# sbc.net
KiCad netlist of a schematic drawn in EAGLE
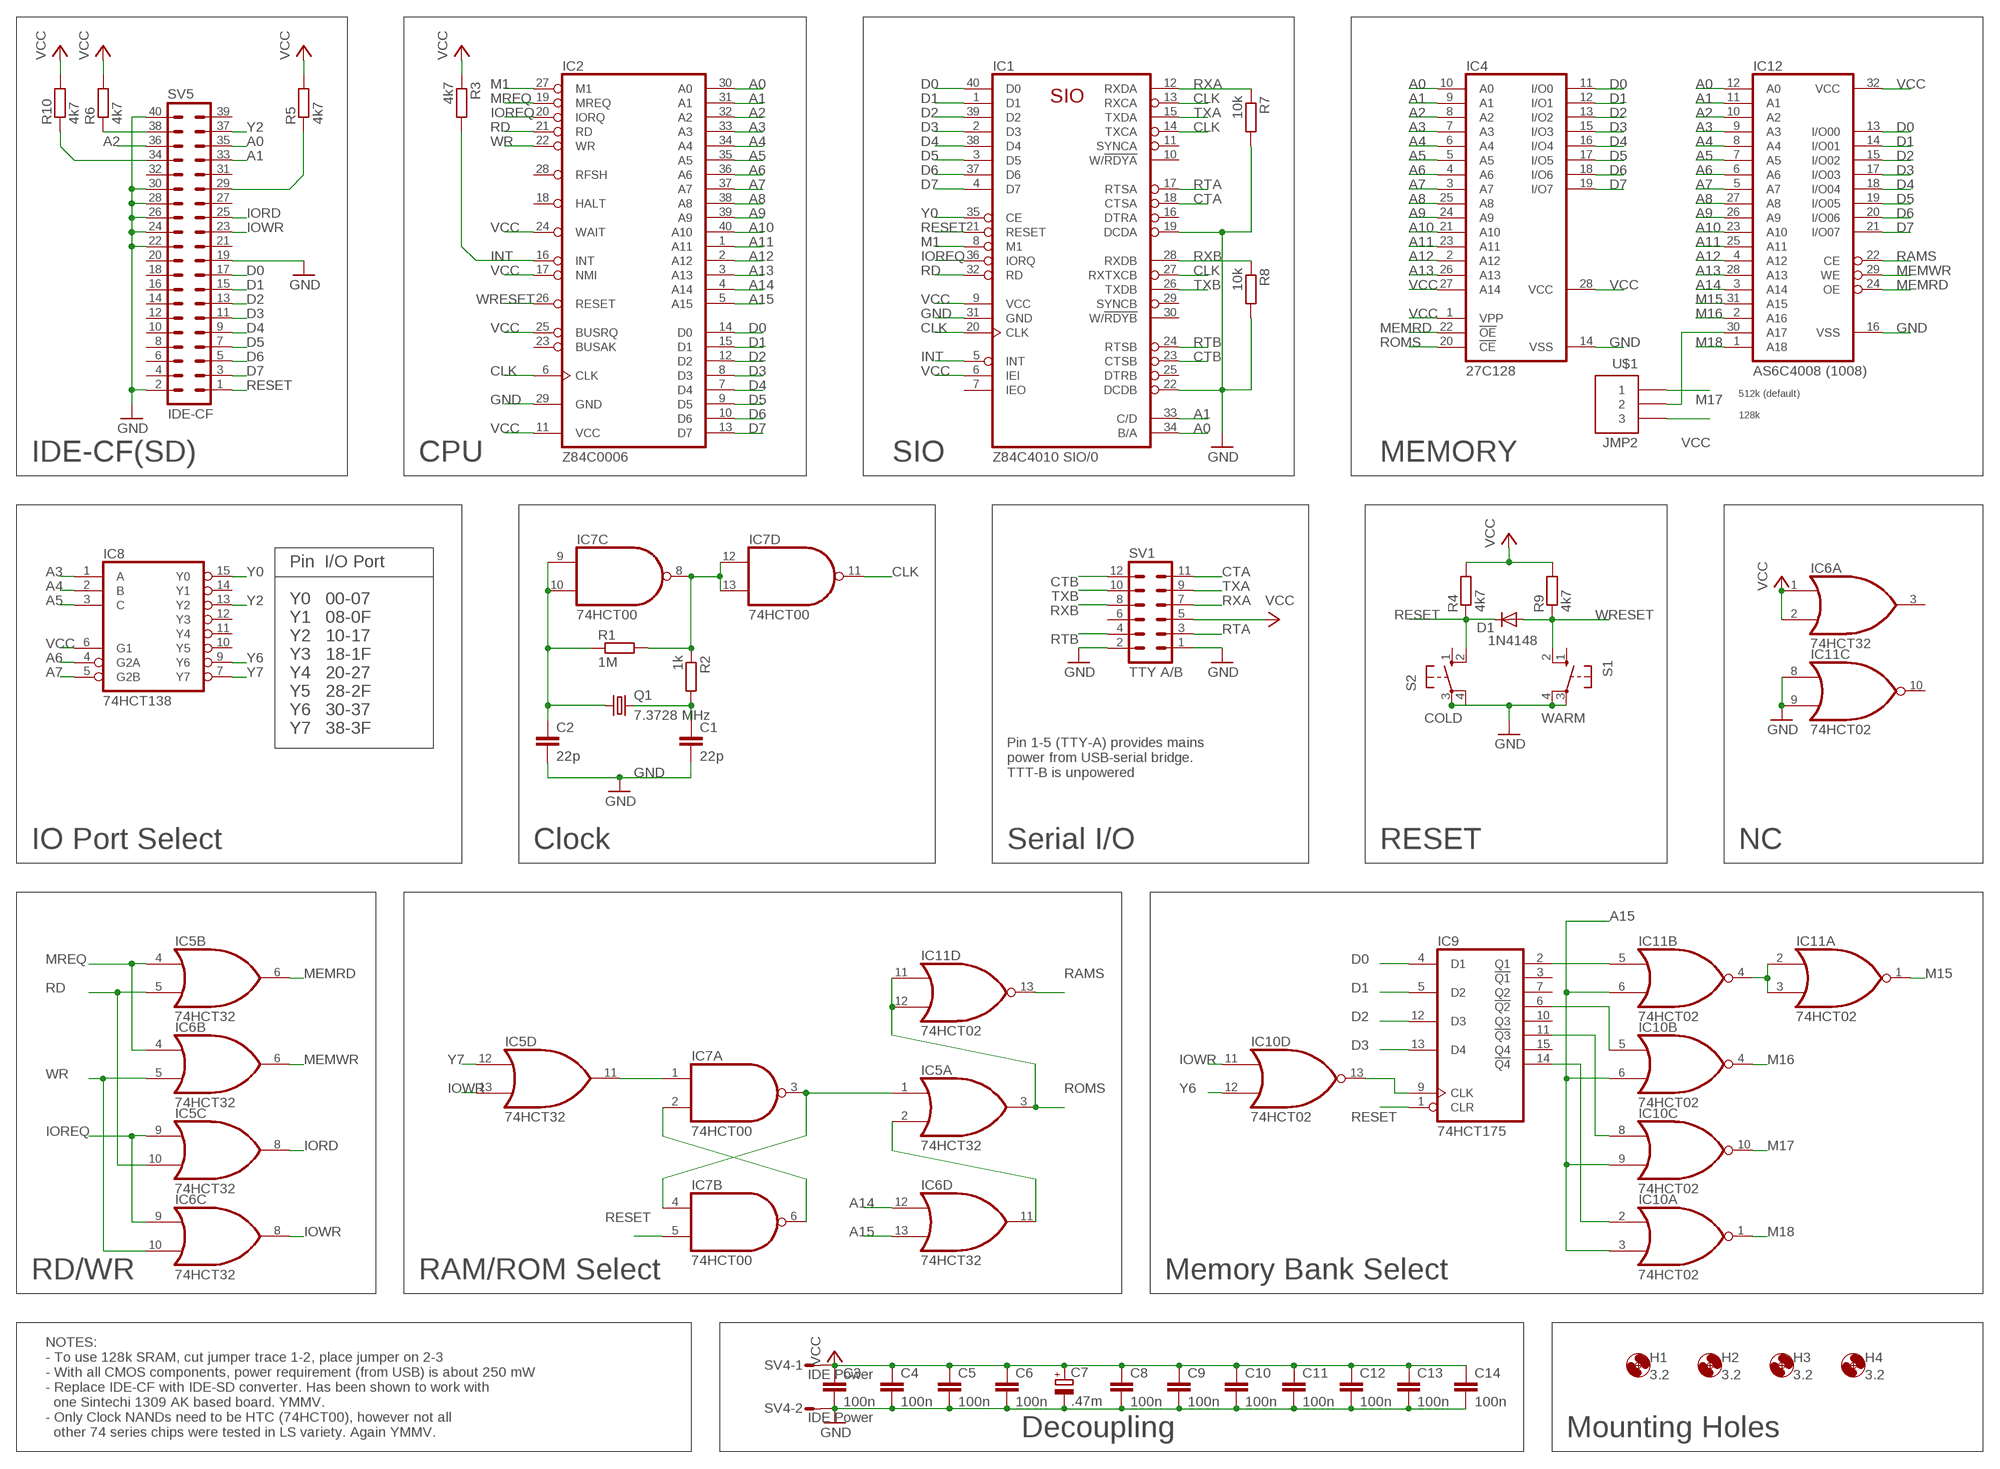
[diagram p0: schematic, sheet 1]

(export (version "E")
  (design (tool "Eeschema 10.0.6"))
  (components
    (comp (ref "C1")
      (value "22p")
      (footprint "eagle-import:C025-024X044")
      (libsource (lib "eagle-import") (part "C-EU025-024X044"))
    )
    (comp (ref "C2")
      (value "22p")
      (footprint "eagle-import:C025-024X044")
      (libsource (lib "eagle-import") (part "C-EU025-024X044"))
    )
    (comp (ref "C3")
      (value "100n")
      (footprint "eagle-import:C050-025X075")
      (libsource (lib "eagle-import") (part "C-EU050-025X075"))
    )
    (comp (ref "C4")
      (value "100n")
      (footprint "eagle-import:C050-025X075")
      (libsource (lib "eagle-import") (part "C-EU050-025X075"))
    )
    (comp (ref "C5")
      (value "100n")
      (footprint "eagle-import:C050-025X075")
      (libsource (lib "eagle-import") (part "C-EU050-025X075"))
    )
    (comp (ref "C6")
      (value "100n")
      (footprint "eagle-import:C050-025X075")
      (libsource (lib "eagle-import") (part "C-EU050-025X075"))
    )
    (comp (ref "C7")
      (value ".47m")
      (footprint "eagle-import:E2,5-6E")
      (libsource (lib "eagle-import") (part "CPOL-EUE2,5-6E"))
    )
    (comp (ref "C8")
      (value "100n")
      (footprint "eagle-import:C050-025X075")
      (libsource (lib "eagle-import") (part "C-EU050-025X075"))
    )
    (comp (ref "C9")
      (value "100n")
      (footprint "eagle-import:C050-025X075")
      (libsource (lib "eagle-import") (part "C-EU050-025X075"))
    )
    (comp (ref "C10")
      (value "100n")
      (footprint "eagle-import:C050-025X075")
      (libsource (lib "eagle-import") (part "C-EU050-025X075"))
    )
    (comp (ref "C11")
      (value "100n")
      (footprint "eagle-import:C050-025X075")
      (libsource (lib "eagle-import") (part "C-EU050-025X075"))
    )
    (comp (ref "C12")
      (value "100n")
      (footprint "eagle-import:C050-025X075")
      (libsource (lib "eagle-import") (part "C-EU050-025X075"))
    )
    (comp (ref "C13")
      (value "100n")
      (footprint "eagle-import:C050-025X075")
      (libsource (lib "eagle-import") (part "C-EU050-025X075"))
    )
    (comp (ref "C14")
      (value "100n")
      (footprint "eagle-import:C050-025X075")
      (libsource (lib "eagle-import") (part "C-EU050-025X075"))
    )
    (comp (ref "D1")
      (value "1N4148")
      (footprint "eagle-import:DO35-7")
      (libsource (lib "eagle-import") (part "1N4148DO35-7"))
    )
    (comp (ref "H1")
      (value "3.2")
      (footprint "eagle-import:3,2")
      (libsource (lib "eagle-import") (part "MOUNT-HOLE3.2"))
    )
    (comp (ref "H2")
      (value "3.2")
      (footprint "eagle-import:3,2")
      (libsource (lib "eagle-import") (part "MOUNT-HOLE3.2"))
    )
    (comp (ref "H3")
      (value "3.2")
      (footprint "eagle-import:3,2")
      (libsource (lib "eagle-import") (part "MOUNT-HOLE3.2"))
    )
    (comp (ref "H4")
      (value "3.2")
      (footprint "eagle-import:3,2")
      (libsource (lib "eagle-import") (part "MOUNT-HOLE3.2"))
    )
    (comp (ref "IC1")
      (value "Z84C4010 SIO/0")
      (footprint "eagle-import:DIL40")
      (libsource (lib "eagle-import") (part "Z80SIO"))
    )
    (comp (ref "IC2")
      (value "Z84C0006")
      (footprint "eagle-import:DIL40")
      (libsource (lib "eagle-import") (part "Z80CPU"))
    )
    (comp (ref "IC4")
      (value "27C128")
      (footprint "eagle-import:DIL28-6")
      (libsource (lib "eagle-import") (part "27C256AG"))
    )
    (comp (ref "IC5")
      (value "74HCT32")
      (footprint "eagle-import:DIL14")
      (libsource (lib "eagle-import") (part "7432NLS"))
    )
    (comp (ref "IC6")
      (value "74HCT32")
      (footprint "eagle-import:DIL14")
      (libsource (lib "eagle-import") (part "7432NLS"))
    )
    (comp (ref "IC7")
      (value "74HCT00")
      (footprint "eagle-import:DIL14")
      (libsource (lib "eagle-import") (part "7400NLS"))
    )
    (comp (ref "IC8")
      (value "74HCT138")
      (footprint "eagle-import:DIL16")
      (libsource (lib "eagle-import") (part "74138NLS"))
    )
    (comp (ref "IC9")
      (value "74HCT175")
      (footprint "eagle-import:DIL16")
      (libsource (lib "eagle-import") (part "74175NLS"))
    )
    (comp (ref "IC10")
      (value "74HCT02")
      (footprint "eagle-import:DIL14")
      (libsource (lib "eagle-import") (part "7402NLS"))
    )
    (comp (ref "IC11")
      (value "74HCT02")
      (footprint "eagle-import:DIL14")
      (libsource (lib "eagle-import") (part "7402NLS"))
    )
    (comp (ref "IC12")
      (value "AS6C4008 (1008)")
      (footprint "eagle-import:DIL32")
      (libsource (lib "eagle-import") (part "HM628512A_DIL32"))
    )
    (comp (ref "Q1")
      (value "7.3728 MHz")
      (footprint "eagle-import:HC49U-V")
      (libsource (lib "eagle-import") (part "CRYSTALHC49U-V"))
    )
    (comp (ref "R1")
      (value "1M")
      (footprint "eagle-import:0207_10")
      (libsource (lib "eagle-import") (part "R-EU_0207/10"))
    )
    (comp (ref "R2")
      (value "1k")
      (footprint "eagle-import:0207_10")
      (libsource (lib "eagle-import") (part "R-EU_0207/10"))
    )
    (comp (ref "R3")
      (value "4k7")
      (footprint "eagle-import:0207_10")
      (libsource (lib "eagle-import") (part "R-EU_0207/10"))
    )
    (comp (ref "R4")
      (value "4k7")
      (footprint "eagle-import:0207_10")
      (libsource (lib "eagle-import") (part "R-EU_0207/10"))
    )
    (comp (ref "R5")
      (value "4k7")
      (footprint "eagle-import:0207_10")
      (libsource (lib "eagle-import") (part "R-EU_0207/10"))
    )
    (comp (ref "R6")
      (value "4k7")
      (footprint "eagle-import:0207_10")
      (libsource (lib "eagle-import") (part "R-EU_0207/10"))
    )
    (comp (ref "R7")
      (value "10k")
      (footprint "eagle-import:0207_10")
      (libsource (lib "eagle-import") (part "R-EU_0207/10"))
    )
    (comp (ref "R8")
      (value "10k")
      (footprint "eagle-import:0207_10")
      (libsource (lib "eagle-import") (part "R-EU_0207/10"))
    )
    (comp (ref "R9")
      (value "4k7")
      (footprint "eagle-import:0207_10")
      (libsource (lib "eagle-import") (part "R-EU_0207/10"))
    )
    (comp (ref "R10")
      (value "4k7")
      (footprint "eagle-import:0207_10")
      (libsource (lib "eagle-import") (part "R-EU_0207/10"))
    )
    (comp (ref "S1")
      (value "WARM")
      (footprint "eagle-import:B3F-10XX")
      (fields (field (name "MPN") "B3F-1000"))
      (libsource (lib "eagle-import") (part "10-XX"))
    )
    (comp (ref "S2")
      (value "COLD")
      (footprint "eagle-import:B3F-10XX")
      (fields (field (name "MPN") "B3F-1000"))
      (libsource (lib "eagle-import") (part "10-XX"))
    )
    (comp (ref "SV1")
      (value "TTY A/B")
      (footprint "eagle-import:MA06-2")
      (libsource (lib "eagle-import") (part "MA06-2"))
    )
    (comp (ref "SV4")
      (value "IDE Power")
      (footprint "eagle-import:S02P")
      (libsource (lib "eagle-import") (part "S02P"))
    )
    (comp (ref "SV5")
      (value "IDE-CF")
      (footprint "eagle-import:MA20-2")
      (libsource (lib "eagle-import") (part "MA20-2"))
    )
    (comp (ref "U$1")
      (value "JMP2")
      (footprint "eagle-import:JUMP2")
      (libsource (lib "eagle-import") (part "JMP2"))
    )
  )
  (nets
    (net (code "1") (name "/A0") (class "Default")
      (node (ref "IC1") (pin "34") (pinfunction "B/A_34") (pintype "input"))
      (node (ref "IC12") (pin "12") (pinfunction "A0_12") (pintype "input"))
      (node (ref "IC2") (pin "30") (pinfunction "A0_30") (pintype "output"))
      (node (ref "IC4") (pin "10") (pinfunction "A0_10") (pintype "input"))
      (node (ref "SV5") (pin "35") (pinfunction "35_35") (pintype "passive"))
    )
    (net (code "2") (name "/A1") (class "Default")
      (node (ref "IC1") (pin "33") (pinfunction "C/D_33") (pintype "input"))
      (node (ref "IC12") (pin "11") (pinfunction "A1_11") (pintype "input"))
      (node (ref "IC2") (pin "31") (pinfunction "A1_31") (pintype "output"))
      (node (ref "IC4") (pin "9") (pinfunction "A1_9") (pintype "input"))
      (node (ref "SV5") (pin "33") (pinfunction "33_33") (pintype "passive"))
    )
    (net (code "3") (name "/A2") (class "Default")
      (node (ref "IC12") (pin "10") (pinfunction "A2_10") (pintype "input"))
      (node (ref "IC2") (pin "32") (pinfunction "A2_32") (pintype "output"))
      (node (ref "IC4") (pin "8") (pinfunction "A2_8") (pintype "input"))
      (node (ref "SV5") (pin "36") (pinfunction "36_36") (pintype "passive"))
    )
    (net (code "4") (name "/A3") (class "Default")
      (node (ref "IC12") (pin "9") (pinfunction "A3_9") (pintype "input"))
      (node (ref "IC2") (pin "33") (pinfunction "A3_33") (pintype "output"))
      (node (ref "IC4") (pin "7") (pinfunction "A3_7") (pintype "input"))
      (node (ref "IC8") (pin "1") (pinfunction "A_1") (pintype "input"))
    )
    (net (code "5") (name "/A4") (class "Default")
      (node (ref "IC12") (pin "8") (pinfunction "A4_8") (pintype "input"))
      (node (ref "IC2") (pin "34") (pinfunction "A4_34") (pintype "output"))
      (node (ref "IC4") (pin "6") (pinfunction "A4_6") (pintype "input"))
      (node (ref "IC8") (pin "2") (pinfunction "B_2") (pintype "input"))
    )
    (net (code "6") (name "/A5") (class "Default")
      (node (ref "IC12") (pin "7") (pinfunction "A5_7") (pintype "input"))
      (node (ref "IC2") (pin "35") (pinfunction "A5_35") (pintype "output"))
      (node (ref "IC4") (pin "5") (pinfunction "A5_5") (pintype "input"))
      (node (ref "IC8") (pin "3") (pinfunction "C_3") (pintype "input"))
    )
    (net (code "7") (name "/A6") (class "Default")
      (node (ref "IC12") (pin "6") (pinfunction "A6_6") (pintype "input"))
      (node (ref "IC2") (pin "36") (pinfunction "A6_36") (pintype "output"))
      (node (ref "IC4") (pin "4") (pinfunction "A6_4") (pintype "input"))
      (node (ref "IC8") (pin "4") (pinfunction "G2A_4") (pintype "input"))
    )
    (net (code "8") (name "/A7") (class "Default")
      (node (ref "IC12") (pin "5") (pinfunction "A7_5") (pintype "input"))
      (node (ref "IC2") (pin "37") (pinfunction "A7_37") (pintype "output"))
      (node (ref "IC4") (pin "3") (pinfunction "A7_3") (pintype "input"))
      (node (ref "IC8") (pin "5") (pinfunction "G2B_5") (pintype "input"))
    )
    (net (code "9") (name "/A8") (class "Default")
      (node (ref "IC12") (pin "27") (pinfunction "A8_27") (pintype "input"))
      (node (ref "IC2") (pin "38") (pinfunction "A8_38") (pintype "output"))
      (node (ref "IC4") (pin "25") (pinfunction "A8_25") (pintype "input"))
    )
    (net (code "10") (name "/A9") (class "Default")
      (node (ref "IC12") (pin "26") (pinfunction "A9_26") (pintype "input"))
      (node (ref "IC2") (pin "39") (pinfunction "A9_39") (pintype "output"))
      (node (ref "IC4") (pin "24") (pinfunction "A9_24") (pintype "input"))
    )
    (net (code "11") (name "/A10") (class "Default")
      (node (ref "IC12") (pin "23") (pinfunction "A10_23") (pintype "input"))
      (node (ref "IC2") (pin "40") (pinfunction "A10_40") (pintype "output"))
      (node (ref "IC4") (pin "21") (pinfunction "A10_21") (pintype "input"))
    )
    (net (code "12") (name "/A11") (class "Default")
      (node (ref "IC12") (pin "25") (pinfunction "A11_25") (pintype "input"))
      (node (ref "IC2") (pin "1") (pinfunction "A11_1") (pintype "output"))
      (node (ref "IC4") (pin "23") (pinfunction "A11_23") (pintype "input"))
    )
    (net (code "13") (name "/A12") (class "Default")
      (node (ref "IC12") (pin "4") (pinfunction "A12_4") (pintype "input"))
      (node (ref "IC2") (pin "2") (pinfunction "A12_2") (pintype "output"))
      (node (ref "IC4") (pin "2") (pinfunction "A12_2") (pintype "input"))
    )
    (net (code "14") (name "/A13") (class "Default")
      (node (ref "IC12") (pin "28") (pinfunction "A13_28") (pintype "input"))
      (node (ref "IC2") (pin "3") (pinfunction "A13_3") (pintype "output"))
      (node (ref "IC4") (pin "26") (pinfunction "A13_26") (pintype "input"))
    )
    (net (code "15") (name "/A14") (class "Default")
      (node (ref "IC12") (pin "3") (pinfunction "A14_3") (pintype "input"))
      (node (ref "IC2") (pin "4") (pinfunction "A14_4") (pintype "output"))
      (node (ref "IC6") (pin "12") (pinfunction "I0_12") (pintype "input"))
    )
    (net (code "16") (name "/A15") (class "Default")
      (node (ref "IC10") (pin "3") (pinfunction "I1_3") (pintype "input"))
      (node (ref "IC10") (pin "6") (pinfunction "I1_6") (pintype "input"))
      (node (ref "IC10") (pin "9") (pinfunction "I1_9") (pintype "input"))
      (node (ref "IC11") (pin "6") (pinfunction "I1_6") (pintype "input"))
      (node (ref "IC2") (pin "5") (pinfunction "A15_5") (pintype "output"))
      (node (ref "IC6") (pin "13") (pinfunction "I1_13") (pintype "input"))
    )
    (net (code "17") (name "/CLK") (class "Default")
      (node (ref "IC1") (pin "13") (pinfunction "RXCA_13") (pintype "input"))
      (node (ref "IC1") (pin "14") (pinfunction "TXCA_14") (pintype "input"))
      (node (ref "IC1") (pin "20") (pinfunction "CLK_20") (pintype "input"))
      (node (ref "IC1") (pin "27") (pinfunction "RXTXCB_27") (pintype "input"))
      (node (ref "IC2") (pin "6") (pinfunction "CLK_6") (pintype "input"))
      (node (ref "IC7") (pin "11") (pinfunction "O_11") (pintype "output"))
    )
    (net (code "18") (name "/CTA") (class "Default")
      (node (ref "IC1") (pin "18") (pinfunction "CTSA_18") (pintype "input"))
      (node (ref "SV1") (pin "11") (pinfunction "11_11") (pintype "passive"))
    )
    (net (code "19") (name "/CTB") (class "Default")
      (node (ref "IC1") (pin "23") (pinfunction "CTSB_23") (pintype "input"))
      (node (ref "SV1") (pin "12") (pinfunction "12_12") (pintype "passive"))
    )
    (net (code "20") (name "/D0") (class "Default")
      (node (ref "IC1") (pin "40") (pinfunction "D0_40") (pintype "bidirectional"))
      (node (ref "IC12") (pin "13") (pinfunction "I/O00_13") (pintype "bidirectional"))
      (node (ref "IC2") (pin "14") (pinfunction "D0_14") (pintype "bidirectional"))
      (node (ref "IC4") (pin "11") (pinfunction "I/O0_11") (pintype "tri_state"))
      (node (ref "IC9") (pin "4") (pinfunction "D1_4") (pintype "input"))
      (node (ref "SV5") (pin "17") (pinfunction "17_17") (pintype "passive"))
    )
    (net (code "21") (name "/D1") (class "Default")
      (node (ref "IC1") (pin "1") (pinfunction "D1_1") (pintype "bidirectional"))
      (node (ref "IC12") (pin "14") (pinfunction "I/O01_14") (pintype "bidirectional"))
      (node (ref "IC2") (pin "15") (pinfunction "D1_15") (pintype "bidirectional"))
      (node (ref "IC4") (pin "12") (pinfunction "I/O1_12") (pintype "tri_state"))
      (node (ref "IC9") (pin "5") (pinfunction "D2_5") (pintype "input"))
      (node (ref "SV5") (pin "15") (pinfunction "15_15") (pintype "passive"))
    )
    (net (code "22") (name "/D2") (class "Default")
      (node (ref "IC1") (pin "39") (pinfunction "D2_39") (pintype "bidirectional"))
      (node (ref "IC12") (pin "15") (pinfunction "I/O02_15") (pintype "bidirectional"))
      (node (ref "IC2") (pin "12") (pinfunction "D2_12") (pintype "bidirectional"))
      (node (ref "IC4") (pin "13") (pinfunction "I/O2_13") (pintype "tri_state"))
      (node (ref "IC9") (pin "12") (pinfunction "D3_12") (pintype "input"))
      (node (ref "SV5") (pin "13") (pinfunction "13_13") (pintype "passive"))
    )
    (net (code "23") (name "/D3") (class "Default")
      (node (ref "IC1") (pin "2") (pinfunction "D3_2") (pintype "bidirectional"))
      (node (ref "IC12") (pin "17") (pinfunction "I/O03_17") (pintype "bidirectional"))
      (node (ref "IC2") (pin "8") (pinfunction "D3_8") (pintype "bidirectional"))
      (node (ref "IC4") (pin "15") (pinfunction "I/O3_15") (pintype "tri_state"))
      (node (ref "IC9") (pin "13") (pinfunction "D4_13") (pintype "input"))
      (node (ref "SV5") (pin "11") (pinfunction "11_11") (pintype "passive"))
    )
    (net (code "24") (name "/D4") (class "Default")
      (node (ref "IC1") (pin "38") (pinfunction "D4_38") (pintype "bidirectional"))
      (node (ref "IC12") (pin "18") (pinfunction "I/O04_18") (pintype "bidirectional"))
      (node (ref "IC2") (pin "7") (pinfunction "D4_7") (pintype "bidirectional"))
      (node (ref "IC4") (pin "16") (pinfunction "I/O4_16") (pintype "tri_state"))
      (node (ref "SV5") (pin "9") (pinfunction "9_9") (pintype "passive"))
    )
    (net (code "25") (name "/D5") (class "Default")
      (node (ref "IC1") (pin "3") (pinfunction "D5_3") (pintype "bidirectional"))
      (node (ref "IC12") (pin "19") (pinfunction "I/O05_19") (pintype "bidirectional"))
      (node (ref "IC2") (pin "9") (pinfunction "D5_9") (pintype "bidirectional"))
      (node (ref "IC4") (pin "17") (pinfunction "I/O5_17") (pintype "tri_state"))
      (node (ref "SV5") (pin "7") (pinfunction "7_7") (pintype "passive"))
    )
    (net (code "26") (name "/D6") (class "Default")
      (node (ref "IC1") (pin "37") (pinfunction "D6_37") (pintype "bidirectional"))
      (node (ref "IC12") (pin "20") (pinfunction "I/O06_20") (pintype "bidirectional"))
      (node (ref "IC2") (pin "10") (pinfunction "D6_10") (pintype "bidirectional"))
      (node (ref "IC4") (pin "18") (pinfunction "I/O6_18") (pintype "tri_state"))
      (node (ref "SV5") (pin "5") (pinfunction "5_5") (pintype "passive"))
    )
    (net (code "27") (name "/D7") (class "Default")
      (node (ref "IC1") (pin "4") (pinfunction "D7_4") (pintype "bidirectional"))
      (node (ref "IC12") (pin "21") (pinfunction "I/O07_21") (pintype "bidirectional"))
      (node (ref "IC2") (pin "13") (pinfunction "D7_13") (pintype "bidirectional"))
      (node (ref "IC4") (pin "19") (pinfunction "I/O7_19") (pintype "tri_state"))
      (node (ref "SV5") (pin "3") (pinfunction "3_3") (pintype "passive"))
    )
    (net (code "28") (name "/INT") (class "Default")
      (node (ref "IC1") (pin "5") (pinfunction "INT_5") (pintype "output"))
      (node (ref "IC2") (pin "16") (pinfunction "INT_16") (pintype "input"))
      (node (ref "R3") (pin "2") (pinfunction "2_2") (pintype "passive"))
    )
    (net (code "29") (name "/IORD") (class "Default")
      (node (ref "IC5") (pin "8") (pinfunction "O_8") (pintype "output"))
      (node (ref "SV5") (pin "25") (pinfunction "25_25") (pintype "passive"))
    )
    (net (code "30") (name "/IOREQ") (class "Default")
      (node (ref "IC1") (pin "36") (pinfunction "IORQ_36") (pintype "input"))
      (node (ref "IC2") (pin "20") (pinfunction "IORQ_20") (pintype "output"))
      (node (ref "IC5") (pin "9") (pinfunction "I0_9") (pintype "input"))
      (node (ref "IC6") (pin "9") (pinfunction "I0_9") (pintype "input"))
    )
    (net (code "31") (name "/IOWR") (class "Default")
      (node (ref "IC10") (pin "11") (pinfunction "I0_11") (pintype "input"))
      (node (ref "IC5") (pin "13") (pinfunction "I1_13") (pintype "input"))
      (node (ref "IC6") (pin "8") (pinfunction "O_8") (pintype "output"))
      (node (ref "SV5") (pin "23") (pinfunction "23_23") (pintype "passive"))
    )
    (net (code "32") (name "/M1") (class "Default")
      (node (ref "IC1") (pin "8") (pinfunction "M1_8") (pintype "input"))
      (node (ref "IC2") (pin "27") (pinfunction "M1_27") (pintype "output"))
    )
    (net (code "33") (name "/M15") (class "Default")
      (node (ref "IC11") (pin "1") (pinfunction "O_1") (pintype "output"))
      (node (ref "IC12") (pin "31") (pinfunction "A15_31") (pintype "input"))
    )
    (net (code "34") (name "/M16") (class "Default")
      (node (ref "IC10") (pin "4") (pinfunction "O_4") (pintype "output"))
      (node (ref "IC12") (pin "2") (pinfunction "A16_2") (pintype "input"))
    )
    (net (code "35") (name "/M17") (class "Default")
      (node (ref "IC10") (pin "10") (pinfunction "O_10") (pintype "output"))
      (node (ref "U$1") (pin "1") (pinfunction "1_1") (pintype "bidirectional"))
    )
    (net (code "36") (name "/M18") (class "Default")
      (node (ref "IC10") (pin "1") (pinfunction "O_1") (pintype "output"))
      (node (ref "IC12") (pin "1") (pinfunction "A18_1") (pintype "input"))
    )
    (net (code "37") (name "/MEMRD") (class "Default")
      (node (ref "IC12") (pin "24") (pinfunction "OE_24") (pintype "input"))
      (node (ref "IC4") (pin "22") (pinfunction "~{OE}_22") (pintype "input"))
      (node (ref "IC5") (pin "6") (pinfunction "O_6") (pintype "output"))
    )
    (net (code "38") (name "/MEMWR") (class "Default")
      (node (ref "IC12") (pin "29") (pinfunction "WE_29") (pintype "input"))
      (node (ref "IC6") (pin "6") (pinfunction "O_6") (pintype "output"))
    )
    (net (code "39") (name "/MREQ") (class "Default")
      (node (ref "IC2") (pin "19") (pinfunction "MREQ_19") (pintype "output"))
      (node (ref "IC5") (pin "4") (pinfunction "I0_4") (pintype "input"))
      (node (ref "IC6") (pin "4") (pinfunction "I0_4") (pintype "input"))
    )
    (net (code "40") (name "/RAMS") (class "Default")
      (node (ref "IC11") (pin "13") (pinfunction "O_13") (pintype "output"))
      (node (ref "IC12") (pin "22") (pinfunction "CE_22") (pintype "input"))
    )
    (net (code "41") (name "/RD") (class "Default")
      (node (ref "IC1") (pin "32") (pinfunction "RD_32") (pintype "input"))
      (node (ref "IC2") (pin "21") (pinfunction "RD_21") (pintype "output"))
      (node (ref "IC5") (pin "10") (pinfunction "I1_10") (pintype "input"))
      (node (ref "IC5") (pin "5") (pinfunction "I1_5") (pintype "input"))
    )
    (net (code "42") (name "/RESET") (class "Default")
      (node (ref "D1") (pin "C") (pinfunction "C_C") (pintype "passive"))
      (node (ref "IC1") (pin "21") (pinfunction "RESET_21") (pintype "input"))
      (node (ref "IC7") (pin "5") (pinfunction "I1_5") (pintype "input"))
      (node (ref "IC9") (pin "1") (pinfunction "CLR_1") (pintype "input"))
      (node (ref "R4") (pin "1") (pinfunction "1_1") (pintype "passive"))
      (node (ref "S2") (pin "2") (pinfunction "S1_2") (pintype "passive"))
      (node (ref "SV5") (pin "1") (pinfunction "1_1") (pintype "passive"))
    )
    (net (code "43") (name "/ROMS") (class "Default")
      (node (ref "IC11") (pin "11") (pinfunction "I0_11") (pintype "input"))
      (node (ref "IC11") (pin "12") (pinfunction "I1_12") (pintype "input"))
      (node (ref "IC4") (pin "20") (pinfunction "~{CE}_20") (pintype "input"))
      (node (ref "IC5") (pin "3") (pinfunction "O_3") (pintype "output"))
    )
    (net (code "44") (name "/RTA") (class "Default")
      (node (ref "IC1") (pin "17") (pinfunction "RTSA_17") (pintype "output"))
      (node (ref "SV1") (pin "3") (pinfunction "3_3") (pintype "passive"))
    )
    (net (code "45") (name "/RTB") (class "Default")
      (node (ref "IC1") (pin "24") (pinfunction "RTSB_24") (pintype "output"))
      (node (ref "SV1") (pin "4") (pinfunction "4_4") (pintype "passive"))
    )
    (net (code "46") (name "/RXA") (class "Default")
      (node (ref "IC1") (pin "12") (pinfunction "RXDA_12") (pintype "input"))
      (node (ref "R7") (pin "1") (pinfunction "1_1") (pintype "passive"))
      (node (ref "SV1") (pin "7") (pinfunction "7_7") (pintype "passive"))
    )
    (net (code "47") (name "/RXB") (class "Default")
      (node (ref "IC1") (pin "28") (pinfunction "RXDB_28") (pintype "input"))
      (node (ref "R8") (pin "1") (pinfunction "1_1") (pintype "passive"))
      (node (ref "SV1") (pin "8") (pinfunction "8_8") (pintype "passive"))
    )
    (net (code "48") (name "/TXA") (class "Default")
      (node (ref "IC1") (pin "15") (pinfunction "TXDA_15") (pintype "input"))
      (node (ref "SV1") (pin "9") (pinfunction "9_9") (pintype "passive"))
    )
    (net (code "49") (name "/TXB") (class "Default")
      (node (ref "IC1") (pin "26") (pinfunction "TXDB_26") (pintype "output"))
      (node (ref "SV1") (pin "10") (pinfunction "10_10") (pintype "passive"))
    )
    (net (code "50") (name "/WR") (class "Default")
      (node (ref "IC2") (pin "22") (pinfunction "WR_22") (pintype "output"))
      (node (ref "IC6") (pin "10") (pinfunction "I1_10") (pintype "input"))
      (node (ref "IC6") (pin "5") (pinfunction "I1_5") (pintype "input"))
    )
    (net (code "51") (name "/WRESET") (class "Default")
      (node (ref "D1") (pin "A") (pinfunction "A_A") (pintype "passive"))
      (node (ref "IC2") (pin "26") (pinfunction "RESET_26") (pintype "input"))
      (node (ref "R9") (pin "1") (pinfunction "1_1") (pintype "passive"))
      (node (ref "S1") (pin "2") (pinfunction "S1_2") (pintype "passive"))
    )
    (net (code "52") (name "/Y0") (class "Default")
      (node (ref "IC1") (pin "35") (pinfunction "CE_35") (pintype "input"))
      (node (ref "IC8") (pin "15") (pinfunction "Y0_15") (pintype "output"))
    )
    (net (code "53") (name "/Y2") (class "Default")
      (node (ref "IC8") (pin "13") (pinfunction "Y2_13") (pintype "output"))
      (node (ref "SV5") (pin "37") (pinfunction "37_37") (pintype "passive"))
    )
    (net (code "54") (name "/Y6") (class "Default")
      (node (ref "IC10") (pin "12") (pinfunction "I1_12") (pintype "input"))
      (node (ref "IC8") (pin "9") (pinfunction "Y6_9") (pintype "output"))
    )
    (net (code "55") (name "/Y7") (class "Default")
      (node (ref "IC5") (pin "12") (pinfunction "I0_12") (pintype "input"))
      (node (ref "IC8") (pin "7") (pinfunction "Y7_7") (pintype "output"))
    )
    (net (code "56") (name "GND") (class "Default")
      (node (ref "C1") (pin "2") (pinfunction "2_2") (pintype "passive"))
      (node (ref "C10") (pin "2") (pinfunction "2_2") (pintype "passive"))
      (node (ref "C11") (pin "2") (pinfunction "2_2") (pintype "passive"))
      (node (ref "C12") (pin "2") (pinfunction "2_2") (pintype "passive"))
      (node (ref "C13") (pin "2") (pinfunction "2_2") (pintype "passive"))
      (node (ref "C14") (pin "2") (pinfunction "2_2") (pintype "passive"))
      (node (ref "C2") (pin "2") (pinfunction "2_2") (pintype "passive"))
      (node (ref "C3") (pin "2") (pinfunction "2_2") (pintype "passive"))
      (node (ref "C4") (pin "2") (pinfunction "2_2") (pintype "passive"))
      (node (ref "C5") (pin "2") (pinfunction "2_2") (pintype "passive"))
      (node (ref "C6") (pin "2") (pinfunction "2_2") (pintype "passive"))
      (node (ref "C7") (pin "-") (pinfunction "-_-") (pintype "passive"))
      (node (ref "C8") (pin "2") (pinfunction "2_2") (pintype "passive"))
      (node (ref "C9") (pin "2") (pinfunction "2_2") (pintype "passive"))
      (node (ref "IC1") (pin "19") (pinfunction "DCDA_19") (pintype "input"))
      (node (ref "IC1") (pin "22") (pinfunction "DCDB_22") (pintype "input"))
      (node (ref "IC1") (pin "31") (pinfunction "GND_31") (pintype "power_in"))
      (node (ref "IC11") (pin "8") (pinfunction "I0_8") (pintype "input"))
      (node (ref "IC11") (pin "9") (pinfunction "I1_9") (pintype "input"))
      (node (ref "IC12") (pin "16") (pinfunction "VSS_16") (pintype "power_in"))
      (node (ref "IC2") (pin "29") (pinfunction "GND_29") (pintype "power_in"))
      (node (ref "IC4") (pin "14") (pinfunction "VSS_14") (pintype "power_in"))
      (node (ref "R7") (pin "2") (pinfunction "2_2") (pintype "passive"))
      (node (ref "R8") (pin "2") (pinfunction "2_2") (pintype "passive"))
      (node (ref "S1") (pin "3") (pinfunction "P_3") (pintype "passive"))
      (node (ref "S1") (pin "4") (pinfunction "P1_4") (pintype "passive"))
      (node (ref "S2") (pin "3") (pinfunction "P_3") (pintype "passive"))
      (node (ref "S2") (pin "4") (pinfunction "P1_4") (pintype "passive"))
      (node (ref "SV1") (pin "1") (pinfunction "1_1") (pintype "passive"))
      (node (ref "SV1") (pin "2") (pinfunction "2_2") (pintype "passive"))
      (node (ref "SV4") (pin "2") (pinfunction "S_2") (pintype "passive"))
      (node (ref "SV5") (pin "19") (pinfunction "19_19") (pintype "passive"))
      (node (ref "SV5") (pin "2") (pinfunction "2_2") (pintype "passive"))
      (node (ref "SV5") (pin "22") (pinfunction "22_22") (pintype "passive"))
      (node (ref "SV5") (pin "24") (pinfunction "24_24") (pintype "passive"))
      (node (ref "SV5") (pin "26") (pinfunction "26_26") (pintype "passive"))
      (node (ref "SV5") (pin "28") (pinfunction "28_28") (pintype "passive"))
      (node (ref "SV5") (pin "30") (pinfunction "30_30") (pintype "passive"))
      (node (ref "SV5") (pin "40") (pinfunction "40_40") (pintype "passive"))
    )
    (net (code "57") (name "Net-(C1-Pad1)") (class "Default")
      (node (ref "C1") (pin "1") (pinfunction "1_1") (pintype "passive"))
      (node (ref "Q1") (pin "2") (pinfunction "2_2") (pintype "passive"))
      (node (ref "R2") (pin "2") (pinfunction "2_2") (pintype "passive"))
    )
    (net (code "58") (name "Net-(IC5A-I0)") (class "Default")
      (node (ref "IC5") (pin "1") (pinfunction "I0_1") (pintype "input"))
      (node (ref "IC7") (pin "3") (pinfunction "O_3") (pintype "output"))
      (node (ref "IC7") (pin "4") (pinfunction "I0_4") (pintype "input"))
    )
    (net (code "59") (name "Net-(IC5A-I1)") (class "Default")
      (node (ref "IC5") (pin "2") (pinfunction "I1_2") (pintype "input"))
      (node (ref "IC6") (pin "11") (pinfunction "O_11") (pintype "output"))
    )
    (net (code "60") (name "Net-(IC5D-O)") (class "Default")
      (node (ref "IC5") (pin "11") (pinfunction "O_11") (pintype "output"))
      (node (ref "IC7") (pin "1") (pinfunction "I0_1") (pintype "input"))
    )
    (net (code "61") (name "Net-(IC7A-I1)") (class "Default")
      (node (ref "IC7") (pin "2") (pinfunction "I1_2") (pintype "input"))
      (node (ref "IC7") (pin "6") (pinfunction "O_6") (pintype "output"))
    )
    (net (code "62") (name "Net-(IC7C-I0)") (class "Default")
      (node (ref "C2") (pin "1") (pinfunction "1_1") (pintype "passive"))
      (node (ref "IC7") (pin "10") (pinfunction "I1_10") (pintype "input"))
      (node (ref "IC7") (pin "9") (pinfunction "I0_9") (pintype "input"))
      (node (ref "Q1") (pin "1") (pinfunction "1_1") (pintype "passive"))
      (node (ref "R1") (pin "1") (pinfunction "1_1") (pintype "passive"))
    )
    (net (code "63") (name "Net-(IC7C-O)") (class "Default")
      (node (ref "IC7") (pin "12") (pinfunction "I0_12") (pintype "input"))
      (node (ref "IC7") (pin "13") (pinfunction "I1_13") (pintype "input"))
      (node (ref "IC7") (pin "8") (pinfunction "O_8") (pintype "output"))
      (node (ref "R1") (pin "2") (pinfunction "2_2") (pintype "passive"))
      (node (ref "R2") (pin "1") (pinfunction "1_1") (pintype "passive"))
    )
    (net (code "64") (name "Net-(IC10A-I0)") (class "Default")
      (node (ref "IC10") (pin "2") (pinfunction "I0_2") (pintype "input"))
      (node (ref "IC9") (pin "14") (pinfunction "~{Q4}_14") (pintype "output"))
    )
    (net (code "65") (name "Net-(IC10B-I0)") (class "Default")
      (node (ref "IC10") (pin "5") (pinfunction "I0_5") (pintype "input"))
      (node (ref "IC9") (pin "6") (pinfunction "~{Q2}_6") (pintype "output"))
    )
    (net (code "66") (name "Net-(IC10C-I0)") (class "Default")
      (node (ref "IC10") (pin "8") (pinfunction "I0_8") (pintype "input"))
      (node (ref "IC9") (pin "11") (pinfunction "~{Q3}_11") (pintype "output"))
    )
    (net (code "67") (name "Net-(IC10D-O)") (class "Default")
      (node (ref "IC10") (pin "13") (pinfunction "O_13") (pintype "output"))
      (node (ref "IC9") (pin "9") (pinfunction "CLK_9") (pintype "input"))
    )
    (net (code "68") (name "Net-(IC11A-I0)") (class "Default")
      (node (ref "IC11") (pin "2") (pinfunction "I0_2") (pintype "input"))
      (node (ref "IC11") (pin "3") (pinfunction "I1_3") (pintype "input"))
      (node (ref "IC11") (pin "4") (pinfunction "O_4") (pintype "output"))
    )
    (net (code "69") (name "Net-(IC11B-I0)") (class "Default")
      (node (ref "IC11") (pin "5") (pinfunction "I0_5") (pintype "input"))
      (node (ref "IC9") (pin "2") (pinfunction "Q1_2") (pintype "output"))
    )
    (net (code "70") (name "Net-(IC12-A17)") (class "Default")
      (node (ref "IC12") (pin "30") (pinfunction "A17_30") (pintype "input"))
      (node (ref "U$1") (pin "2") (pinfunction "2_2") (pintype "bidirectional"))
    )
    (net (code "71") (name "Net-(R5-Pad1)") (class "Default")
      (node (ref "R5") (pin "1") (pinfunction "1_1") (pintype "passive"))
      (node (ref "SV5") (pin "29") (pinfunction "29_29") (pintype "passive"))
    )
    (net (code "72") (name "Net-(R6-Pad1)") (class "Default")
      (node (ref "R6") (pin "1") (pinfunction "1_1") (pintype "passive"))
      (node (ref "SV5") (pin "38") (pinfunction "38_38") (pintype "passive"))
    )
    (net (code "73") (name "Net-(R10-Pad1)") (class "Default")
      (node (ref "R10") (pin "1") (pinfunction "1_1") (pintype "passive"))
      (node (ref "SV5") (pin "34") (pinfunction "34_34") (pintype "passive"))
    )
    (net (code "74") (name "VCC") (class "Default")
      (node (ref "C10") (pin "1") (pinfunction "1_1") (pintype "passive"))
      (node (ref "C11") (pin "1") (pinfunction "1_1") (pintype "passive"))
      (node (ref "C12") (pin "1") (pinfunction "1_1") (pintype "passive"))
      (node (ref "C13") (pin "1") (pinfunction "1_1") (pintype "passive"))
      (node (ref "C14") (pin "1") (pinfunction "1_1") (pintype "passive"))
      (node (ref "C3") (pin "1") (pinfunction "1_1") (pintype "passive"))
      (node (ref "C4") (pin "1") (pinfunction "1_1") (pintype "passive"))
      (node (ref "C5") (pin "1") (pinfunction "1_1") (pintype "passive"))
      (node (ref "C6") (pin "1") (pinfunction "1_1") (pintype "passive"))
      (node (ref "C7") (pin "+") (pinfunction "+_+") (pintype "passive"))
      (node (ref "C8") (pin "1") (pinfunction "1_1") (pintype "passive"))
      (node (ref "C9") (pin "1") (pinfunction "1_1") (pintype "passive"))
      (node (ref "IC1") (pin "6") (pinfunction "IEI_6") (pintype "input"))
      (node (ref "IC1") (pin "9") (pinfunction "VCC_9") (pintype "power_in"))
      (node (ref "IC12") (pin "32") (pinfunction "VCC_32") (pintype "power_in"))
      (node (ref "IC2") (pin "11") (pinfunction "VCC_11") (pintype "power_in"))
      (node (ref "IC2") (pin "17") (pinfunction "NMI_17") (pintype "input"))
      (node (ref "IC2") (pin "24") (pinfunction "WAIT_24") (pintype "input"))
      (node (ref "IC2") (pin "25") (pinfunction "BUSRQ_25") (pintype "input"))
      (node (ref "IC4") (pin "1") (pinfunction "VPP_1") (pintype "input"))
      (node (ref "IC4") (pin "27") (pinfunction "A14_27") (pintype "input"))
      (node (ref "IC4") (pin "28") (pinfunction "VCC_28") (pintype "power_in"))
      (node (ref "IC6") (pin "1") (pinfunction "I0_1") (pintype "input"))
      (node (ref "IC6") (pin "2") (pinfunction "I1_2") (pintype "input"))
      (node (ref "IC8") (pin "6") (pinfunction "G1_6") (pintype "input"))
      (node (ref "R10") (pin "2") (pinfunction "2_2") (pintype "passive"))
      (node (ref "R3") (pin "1") (pinfunction "1_1") (pintype "passive"))
      (node (ref "R4") (pin "2") (pinfunction "2_2") (pintype "passive"))
      (node (ref "R5") (pin "2") (pinfunction "2_2") (pintype "passive"))
      (node (ref "R6") (pin "2") (pinfunction "2_2") (pintype "passive"))
      (node (ref "R9") (pin "2") (pinfunction "2_2") (pintype "passive"))
      (node (ref "SV1") (pin "5") (pinfunction "5_5") (pintype "passive"))
      (node (ref "SV4") (pin "1") (pinfunction "S_1") (pintype "passive"))
      (node (ref "U$1") (pin "3") (pinfunction "3_3") (pintype "bidirectional"))
    )
    (net (code "75") (name "unconnected-(IC1-DTRA-Pad16)") (class "Default")
      (node (ref "IC1") (pin "16") (pinfunction "DTRA_16") (pintype "output"))
    )
    (net (code "76") (name "unconnected-(IC1-DTRB-Pad25)") (class "Default")
      (node (ref "IC1") (pin "25") (pinfunction "DTRB_25") (pintype "output"))
    )
    (net (code "77") (name "unconnected-(IC1-IEO-Pad7)") (class "Default")
      (node (ref "IC1") (pin "7") (pinfunction "IEO_7") (pintype "output"))
    )
    (net (code "78") (name "unconnected-(IC1-SYNCA-Pad11)") (class "Default")
      (node (ref "IC1") (pin "11") (pinfunction "SYNCA_11") (pintype "bidirectional"))
    )
    (net (code "79") (name "unconnected-(IC1-SYNCB-Pad29)") (class "Default")
      (node (ref "IC1") (pin "29") (pinfunction "SYNCB_29") (pintype "bidirectional"))
    )
    (net (code "80") (name "unconnected-(IC1-W{slash}~{RDYA}-Pad10)") (class "Default")
      (node (ref "IC1") (pin "10") (pinfunction "W/~{RDYA}_10") (pintype "output"))
    )
    (net (code "81") (name "unconnected-(IC1-W{slash}~{RDYB}-Pad30)") (class "Default")
      (node (ref "IC1") (pin "30") (pinfunction "W/~{RDYB}_30") (pintype "output"))
    )
    (net (code "82") (name "unconnected-(IC2-BUSAK-Pad23)") (class "Default")
      (node (ref "IC2") (pin "23") (pinfunction "BUSAK_23") (pintype "output"))
    )
    (net (code "83") (name "unconnected-(IC2-HALT-Pad18)") (class "Default")
      (node (ref "IC2") (pin "18") (pinfunction "HALT_18") (pintype "output"))
    )
    (net (code "84") (name "unconnected-(IC2-RFSH-Pad28)") (class "Default")
      (node (ref "IC2") (pin "28") (pinfunction "RFSH_28") (pintype "output"))
    )
    (net (code "85") (name "unconnected-(IC6A-O-Pad3)") (class "Default")
      (node (ref "IC6") (pin "3") (pinfunction "O_3") (pintype "output"))
    )
    (net (code "86") (name "unconnected-(IC8A-Y1-Pad14)") (class "Default")
      (node (ref "IC8") (pin "14") (pinfunction "Y1_14") (pintype "output"))
    )
    (net (code "87") (name "unconnected-(IC8A-Y3-Pad12)") (class "Default")
      (node (ref "IC8") (pin "12") (pinfunction "Y3_12") (pintype "output"))
    )
    (net (code "88") (name "unconnected-(IC8A-Y4-Pad11)") (class "Default")
      (node (ref "IC8") (pin "11") (pinfunction "Y4_11") (pintype "output"))
    )
    (net (code "89") (name "unconnected-(IC8A-Y5-Pad10)") (class "Default")
      (node (ref "IC8") (pin "10") (pinfunction "Y5_10") (pintype "output"))
    )
    (net (code "90") (name "unconnected-(IC9A-Q2-Pad7)") (class "Default")
      (node (ref "IC9") (pin "7") (pinfunction "Q2_7") (pintype "output"))
    )
    (net (code "91") (name "unconnected-(IC9A-Q3-Pad10)") (class "Default")
      (node (ref "IC9") (pin "10") (pinfunction "Q3_10") (pintype "output"))
    )
    (net (code "92") (name "unconnected-(IC9A-Q4-Pad15)") (class "Default")
      (node (ref "IC9") (pin "15") (pinfunction "Q4_15") (pintype "output"))
    )
    (net (code "93") (name "unconnected-(IC9A-~{Q1}-Pad3)") (class "Default")
      (node (ref "IC9") (pin "3") (pinfunction "~{Q1}_3") (pintype "output"))
    )
    (net (code "94") (name "unconnected-(IC11C-O-Pad10)") (class "Default")
      (node (ref "IC11") (pin "10") (pinfunction "O_10") (pintype "output"))
    )
    (net (code "95") (name "unconnected-(S1-S-Pad1)") (class "Default")
      (node (ref "S1") (pin "1") (pinfunction "S_1") (pintype "passive"))
    )
    (net (code "96") (name "unconnected-(S2-S-Pad1)") (class "Default")
      (node (ref "S2") (pin "1") (pinfunction "S_1") (pintype "passive"))
    )
    (net (code "97") (name "unconnected-(SV1-Pad6)") (class "Default")
      (node (ref "SV1") (pin "6") (pinfunction "6_6") (pintype "passive"))
    )
    (net (code "98") (name "unconnected-(SV5-Pad4)") (class "Default")
      (node (ref "SV5") (pin "4") (pinfunction "4_4") (pintype "passive"))
    )
    (net (code "99") (name "unconnected-(SV5-Pad6)") (class "Default")
      (node (ref "SV5") (pin "6") (pinfunction "6_6") (pintype "passive"))
    )
    (net (code "100") (name "unconnected-(SV5-Pad8)") (class "Default")
      (node (ref "SV5") (pin "8") (pinfunction "8_8") (pintype "passive"))
    )
    (net (code "101") (name "unconnected-(SV5-Pad10)") (class "Default")
      (node (ref "SV5") (pin "10") (pinfunction "10_10") (pintype "passive"))
    )
    (net (code "102") (name "unconnected-(SV5-Pad12)") (class "Default")
      (node (ref "SV5") (pin "12") (pinfunction "12_12") (pintype "passive"))
    )
    (net (code "103") (name "unconnected-(SV5-Pad14)") (class "Default")
      (node (ref "SV5") (pin "14") (pinfunction "14_14") (pintype "passive"))
    )
    (net (code "104") (name "unconnected-(SV5-Pad16)") (class "Default")
      (node (ref "SV5") (pin "16") (pinfunction "16_16") (pintype "passive"))
    )
    (net (code "105") (name "unconnected-(SV5-Pad18)") (class "Default")
      (node (ref "SV5") (pin "18") (pinfunction "18_18") (pintype "passive"))
    )
    (net (code "106") (name "unconnected-(SV5-Pad20)") (class "Default")
      (node (ref "SV5") (pin "20") (pinfunction "20_20") (pintype "passive"))
    )
    (net (code "107") (name "unconnected-(SV5-Pad21)") (class "Default")
      (node (ref "SV5") (pin "21") (pinfunction "21_21") (pintype "passive"))
    )
    (net (code "108") (name "unconnected-(SV5-Pad27)") (class "Default")
      (node (ref "SV5") (pin "27") (pinfunction "27_27") (pintype "passive"))
    )
    (net (code "109") (name "unconnected-(SV5-Pad31)") (class "Default")
      (node (ref "SV5") (pin "31") (pinfunction "31_31") (pintype "passive"))
    )
    (net (code "110") (name "unconnected-(SV5-Pad32)") (class "Default")
      (node (ref "SV5") (pin "32") (pinfunction "32_32") (pintype "passive"))
    )
    (net (code "111") (name "unconnected-(SV5-Pad39)") (class "Default")
      (node (ref "SV5") (pin "39") (pinfunction "39_39") (pintype "passive"))
    )
  )
)
